# A604F.net
KiCad netlist of a schematic drawn in EAGLE
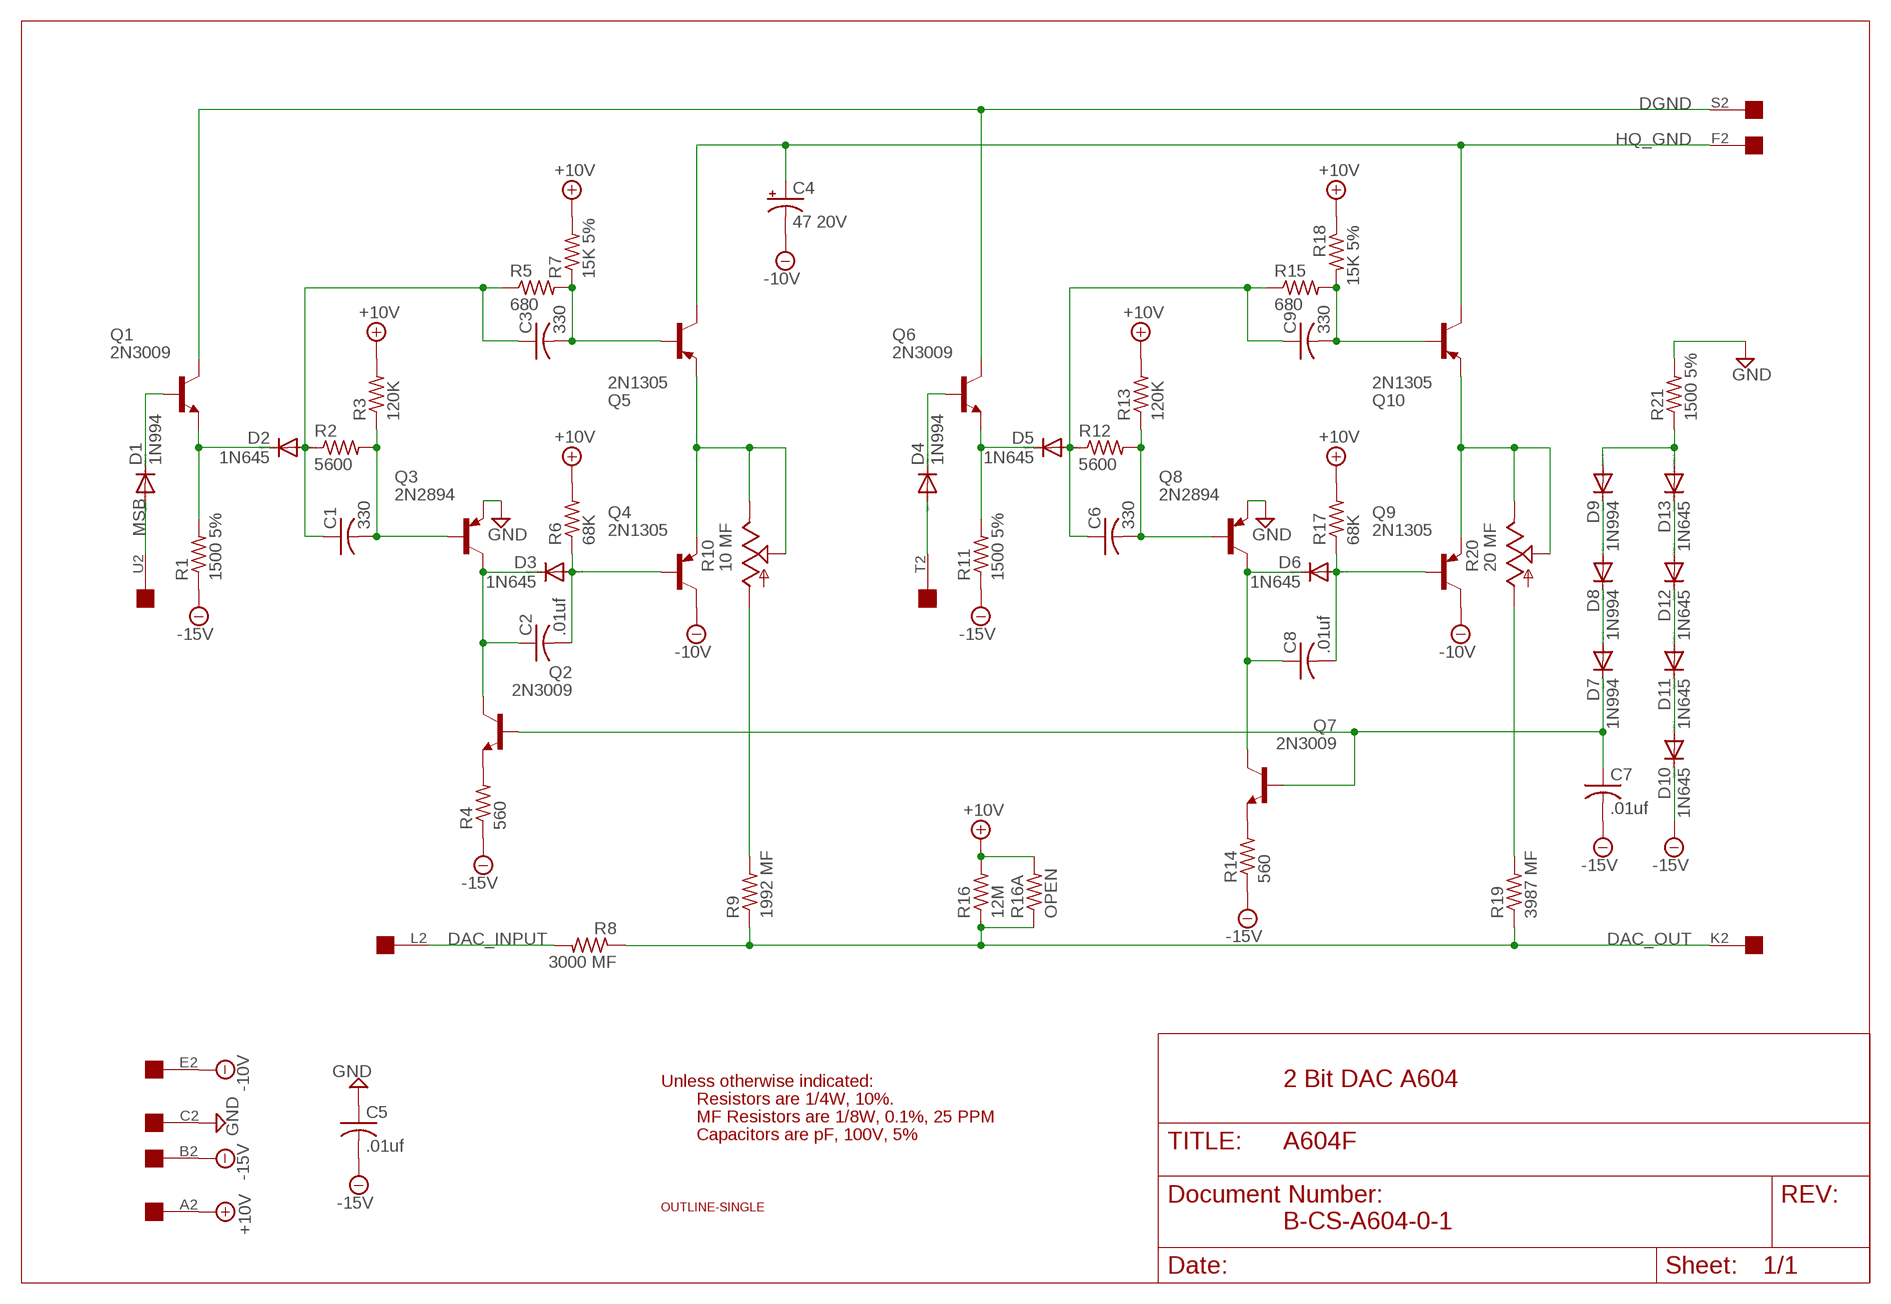
[diagram p0: schematic, sheet 1]

(export (version "E")
  (design (tool "Eeschema 10.0.6"))
  (components
    (comp (ref "C1")
      (value "330")
      (footprint "eagle-import:C075-032X103")
      (libsource (lib "eagle-import") (part "C-US075-032X103"))
    )
    (comp (ref "C2")
      (value ".01uf")
      (footprint "eagle-import:C050-025X075")
      (libsource (lib "eagle-import") (part "C-US050-025X075"))
    )
    (comp (ref "C3")
      (value "330")
      (footprint "eagle-import:C075-032X103")
      (libsource (lib "eagle-import") (part "C-US075-032X103"))
    )
    (comp (ref "C4")
      (value "47 20V")
      (footprint "eagle-import:E12-8")
      (libsource (lib "eagle-import") (part "CPOL-USE20-8AXIAL"))
    )
    (comp (ref "C5")
      (value ".01uf")
      (footprint "eagle-import:C050-025X075")
      (libsource (lib "eagle-import") (part "C-US050-025X075"))
    )
    (comp (ref "C6")
      (value "330")
      (footprint "eagle-import:C075-032X103")
      (libsource (lib "eagle-import") (part "C-US075-032X103"))
    )
    (comp (ref "C7")
      (value ".01uf")
      (footprint "eagle-import:C050-025X075")
      (libsource (lib "eagle-import") (part "C-US050-025X075"))
    )
    (comp (ref "C8")
      (value ".01uf")
      (footprint "eagle-import:C050-025X075")
      (libsource (lib "eagle-import") (part "C-US050-025X075"))
    )
    (comp (ref "C9")
      (value "330")
      (footprint "eagle-import:C075-032X103")
      (libsource (lib "eagle-import") (part "C-US075-032X103"))
    )
    (comp (ref "D1")
      (value "1N994")
      (footprint "eagle-import:DO35-10")
      (libsource (lib "eagle-import") (part "1N4148DO35-10"))
    )
    (comp (ref "D2")
      (value "1N645")
      (footprint "eagle-import:DO35-10")
      (libsource (lib "eagle-import") (part "1N4148DO35-10"))
    )
    (comp (ref "D3")
      (value "1N645")
      (footprint "eagle-import:DO35-10")
      (libsource (lib "eagle-import") (part "1N4148DO35-10"))
    )
    (comp (ref "D4")
      (value "1N994")
      (footprint "eagle-import:DO35-10")
      (libsource (lib "eagle-import") (part "1N4148DO35-10"))
    )
    (comp (ref "D5")
      (value "1N645")
      (footprint "eagle-import:DO35-10")
      (libsource (lib "eagle-import") (part "1N4148DO35-10"))
    )
    (comp (ref "D6")
      (value "1N645")
      (footprint "eagle-import:DO35-10")
      (libsource (lib "eagle-import") (part "1N4148DO35-10"))
    )
    (comp (ref "D7")
      (value "1N994")
      (footprint "eagle-import:DO35-10")
      (libsource (lib "eagle-import") (part "1N4148DO35-10"))
    )
    (comp (ref "D8")
      (value "1N994")
      (footprint "eagle-import:DO35-10")
      (libsource (lib "eagle-import") (part "1N4148DO35-10"))
    )
    (comp (ref "D9")
      (value "1N994")
      (footprint "eagle-import:DO35-10")
      (libsource (lib "eagle-import") (part "1N4148DO35-10"))
    )
    (comp (ref "D10")
      (value "1N645")
      (footprint "eagle-import:DO35-10")
      (libsource (lib "eagle-import") (part "1N4148DO35-10"))
    )
    (comp (ref "D11")
      (value "1N645")
      (footprint "eagle-import:DO35-10")
      (libsource (lib "eagle-import") (part "1N4148DO35-10"))
    )
    (comp (ref "D12")
      (value "1N645")
      (footprint "eagle-import:DO35-10")
      (libsource (lib "eagle-import") (part "1N4148DO35-10"))
    )
    (comp (ref "D13")
      (value "1N645")
      (footprint "eagle-import:DO35-10")
      (libsource (lib "eagle-import") (part "1N4148DO35-10"))
    )
    (comp (ref "Q1")
      (value "2N3009")
      (footprint "eagle-import:TO39")
      (libsource (lib "eagle-import") (part "-NPN-TO39-EBC2N1613"))
    )
    (comp (ref "Q2")
      (value "2N3009")
      (footprint "eagle-import:TO39")
      (libsource (lib "eagle-import") (part "-NPN-TO39-EBC2N1613"))
    )
    (comp (ref "Q3")
      (value "2N2894")
      (footprint "eagle-import:TO39")
      (libsource (lib "eagle-import") (part "2N2904A"))
    )
    (comp (ref "Q4")
      (value "2N1305")
      (footprint "eagle-import:TO39")
      (libsource (lib "eagle-import") (part "2N2904A"))
    )
    (comp (ref "Q5")
      (value "2N1305")
      (footprint "eagle-import:TO39")
      (libsource (lib "eagle-import") (part "2N2904A"))
    )
    (comp (ref "Q6")
      (value "2N3009")
      (footprint "eagle-import:TO39")
      (libsource (lib "eagle-import") (part "-NPN-TO39-EBC2N1613"))
    )
    (comp (ref "Q7")
      (value "2N3009")
      (footprint "eagle-import:TO39")
      (libsource (lib "eagle-import") (part "-NPN-TO39-EBC2N1613"))
    )
    (comp (ref "Q8")
      (value "2N2894")
      (footprint "eagle-import:TO39")
      (libsource (lib "eagle-import") (part "2N2904A"))
    )
    (comp (ref "Q9")
      (value "2N1305")
      (footprint "eagle-import:TO39")
      (libsource (lib "eagle-import") (part "2N2904A"))
    )
    (comp (ref "Q10")
      (value "2N1305")
      (footprint "eagle-import:TO39")
      (libsource (lib "eagle-import") (part "2N2904A"))
    )
    (comp (ref "R1")
      (value "1500 5%")
      (footprint "eagle-import:0207_10")
      (libsource (lib "eagle-import") (part "R-US_0207/10"))
    )
    (comp (ref "R2")
      (value "5600")
      (footprint "eagle-import:0207_10")
      (libsource (lib "eagle-import") (part "R-US_0207/10"))
    )
    (comp (ref "R3")
      (value "120K")
      (footprint "eagle-import:0207_10")
      (libsource (lib "eagle-import") (part "R-US_0207/10"))
    )
    (comp (ref "R4")
      (value "560")
      (footprint "eagle-import:0207_10")
      (libsource (lib "eagle-import") (part "R-US_0207/10"))
    )
    (comp (ref "R5")
      (value "680")
      (footprint "eagle-import:0207_10")
      (libsource (lib "eagle-import") (part "R-US_0207/10"))
    )
    (comp (ref "R6")
      (value "68K")
      (footprint "eagle-import:0207_10")
      (libsource (lib "eagle-import") (part "R-US_0207/10"))
    )
    (comp (ref "R7")
      (value "15K 5%")
      (footprint "eagle-import:0207_10")
      (libsource (lib "eagle-import") (part "R-US_0207/10"))
    )
    (comp (ref "R8")
      (value "3000 MF")
      (footprint "eagle-import:0207_15")
      (libsource (lib "eagle-import") (part "R-US_0207/15"))
    )
    (comp (ref "R9")
      (value "1992 MF")
      (footprint "eagle-import:0207_15")
      (libsource (lib "eagle-import") (part "R-US_0207/15"))
    )
    (comp (ref "R10")
      (value "10 MF")
      (footprint "eagle-import:S75P")
      (libsource (lib "eagle-import") (part "TRIM_US-S75P"))
    )
    (comp (ref "R11")
      (value "1500 5%")
      (footprint "eagle-import:0207_10")
      (libsource (lib "eagle-import") (part "R-US_0207/10"))
    )
    (comp (ref "R12")
      (value "5600")
      (footprint "eagle-import:0207_10")
      (libsource (lib "eagle-import") (part "R-US_0207/10"))
    )
    (comp (ref "R13")
      (value "120K")
      (footprint "eagle-import:0207_10")
      (libsource (lib "eagle-import") (part "R-US_0207/10"))
    )
    (comp (ref "R14")
      (value "560")
      (footprint "eagle-import:0207_10")
      (libsource (lib "eagle-import") (part "R-US_0207/10"))
    )
    (comp (ref "R15")
      (value "680")
      (footprint "eagle-import:0207_10")
      (libsource (lib "eagle-import") (part "R-US_0207/10"))
    )
    (comp (ref "R16")
      (value "12M")
      (footprint "eagle-import:0207_10")
      (libsource (lib "eagle-import") (part "R-US_0207/10"))
    )
    (comp (ref "R16A")
      (value "OPEN")
      (footprint "eagle-import:0207_15")
      (libsource (lib "eagle-import") (part "R-US_0207/15"))
    )
    (comp (ref "R17")
      (value "68K")
      (footprint "eagle-import:0207_10")
      (libsource (lib "eagle-import") (part "R-US_0207/10"))
    )
    (comp (ref "R18")
      (value "15K 5%")
      (footprint "eagle-import:0207_10")
      (libsource (lib "eagle-import") (part "R-US_0207/10"))
    )
    (comp (ref "R19")
      (value "3987 MF")
      (footprint "eagle-import:0207_15")
      (libsource (lib "eagle-import") (part "R-US_0207/15"))
    )
    (comp (ref "R20")
      (value "20 MF")
      (footprint "eagle-import:S75P")
      (libsource (lib "eagle-import") (part "TRIM_US-S75P"))
    )
    (comp (ref "R21")
      (value "1500 5%")
      (footprint "eagle-import:0207_10")
      (libsource (lib "eagle-import") (part "R-US_0207/10"))
    )
    (comp (ref "U$1")
      (value "OUTLINE-SINGLE")
      (footprint "eagle-import:SINGLE")
      (libsource (lib "eagle-import") (part "OUTLINE-SINGLE"))
    )
    (comp (ref "U$3")
      (value "EDGE-1")
      (footprint "eagle-import:EDGE-CON1")
      (libsource (lib "eagle-import") (part "EDGE-1"))
    )
  )
  (nets
    (net (code "1") (name "+10V") (class "Default")
      (node (ref "R13") (pin "2") (pinfunction "2_2") (pintype "passive"))
      (node (ref "R16") (pin "2") (pinfunction "2_2") (pintype "passive"))
      (node (ref "R16A") (pin "2") (pinfunction "2_2") (pintype "passive"))
      (node (ref "R17") (pin "2") (pinfunction "2_2") (pintype "passive"))
      (node (ref "R18") (pin "1") (pinfunction "1_1") (pintype "passive"))
      (node (ref "R3") (pin "2") (pinfunction "2_2") (pintype "passive"))
      (node (ref "R6") (pin "2") (pinfunction "2_2") (pintype "passive"))
      (node (ref "R7") (pin "2") (pinfunction "2_2") (pintype "passive"))
      (node (ref "U$3") (pin "A2") (pinfunction "1_A2") (pintype "bidirectional"))
    )
    (net (code "2") (name "-10V") (class "Default")
      (node (ref "C4") (pin "-") (pinfunction "-_-") (pintype "passive"))
      (node (ref "Q4") (pin "3") (pinfunction "C_3") (pintype "passive"))
      (node (ref "Q9") (pin "3") (pinfunction "C_3") (pintype "passive"))
      (node (ref "U$3") (pin "E2") (pinfunction "1_E2") (pintype "bidirectional"))
    )
    (net (code "3") (name "-15V") (class "Default")
      (node (ref "C5") (pin "2") (pinfunction "2_2") (pintype "passive"))
      (node (ref "C7") (pin "2") (pinfunction "2_2") (pintype "passive"))
      (node (ref "D10") (pin "C") (pinfunction "C_C") (pintype "passive"))
      (node (ref "R1") (pin "1") (pinfunction "1_1") (pintype "passive"))
      (node (ref "R11") (pin "1") (pinfunction "1_1") (pintype "passive"))
      (node (ref "R14") (pin "1") (pinfunction "1_1") (pintype "passive"))
      (node (ref "R4") (pin "1") (pinfunction "1_1") (pintype "passive"))
      (node (ref "U$3") (pin "B2") (pinfunction "1_B2") (pintype "bidirectional"))
    )
    (net (code "4") (name "/DAC_INPUT") (class "Default")
      (node (ref "R8") (pin "2") (pinfunction "2_2") (pintype "passive"))
      (node (ref "U$3") (pin "L2") (pinfunction "1_L2") (pintype "bidirectional"))
    )
    (net (code "5") (name "/DAC_OUT") (class "Default")
      (node (ref "R16") (pin "1") (pinfunction "1_1") (pintype "passive"))
      (node (ref "R16A") (pin "1") (pinfunction "1_1") (pintype "passive"))
      (node (ref "R19") (pin "1") (pinfunction "1_1") (pintype "passive"))
      (node (ref "R8") (pin "1") (pinfunction "1_1") (pintype "passive"))
      (node (ref "R9") (pin "1") (pinfunction "1_1") (pintype "passive"))
      (node (ref "U$3") (pin "K2") (pinfunction "1_K2") (pintype "bidirectional"))
    )
    (net (code "6") (name "/DGND") (class "Default")
      (node (ref "Q1") (pin "3") (pinfunction "C_3") (pintype "passive"))
      (node (ref "Q6") (pin "3") (pinfunction "C_3") (pintype "passive"))
      (node (ref "U$3") (pin "S2") (pinfunction "1_S2") (pintype "bidirectional"))
    )
    (net (code "7") (name "/HQ_GND") (class "Default")
      (node (ref "C4") (pin "+") (pinfunction "+_+") (pintype "passive"))
      (node (ref "Q10") (pin "3") (pinfunction "C_3") (pintype "passive"))
      (node (ref "Q5") (pin "3") (pinfunction "C_3") (pintype "passive"))
      (node (ref "U$3") (pin "F2") (pinfunction "1_F2") (pintype "bidirectional"))
    )
    (net (code "8") (name "/MSB") (class "Default")
      (node (ref "D1") (pin "A") (pinfunction "A_A") (pintype "passive"))
      (node (ref "U$3") (pin "U2") (pinfunction "1_U2") (pintype "bidirectional"))
    )
    (net (code "9") (name "GND") (class "Default")
      (node (ref "C5") (pin "1") (pinfunction "1_1") (pintype "passive"))
      (node (ref "Q3") (pin "1") (pinfunction "E_1") (pintype "passive"))
      (node (ref "Q8") (pin "1") (pinfunction "E_1") (pintype "passive"))
      (node (ref "R21") (pin "2") (pinfunction "2_2") (pintype "passive"))
      (node (ref "U$3") (pin "C2") (pinfunction "1_C2") (pintype "bidirectional"))
    )
    (net (code "10") (name "Net-(C1-Pad1)") (class "Default")
      (node (ref "C1") (pin "1") (pinfunction "1_1") (pintype "passive"))
      (node (ref "C3") (pin "1") (pinfunction "1_1") (pintype "passive"))
      (node (ref "D2") (pin "A") (pinfunction "A_A") (pintype "passive"))
      (node (ref "R2") (pin "1") (pinfunction "1_1") (pintype "passive"))
      (node (ref "R5") (pin "1") (pinfunction "1_1") (pintype "passive"))
    )
    (net (code "11") (name "Net-(C6-Pad1)") (class "Default")
      (node (ref "C6") (pin "1") (pinfunction "1_1") (pintype "passive"))
      (node (ref "C9") (pin "1") (pinfunction "1_1") (pintype "passive"))
      (node (ref "D5") (pin "A") (pinfunction "A_A") (pintype "passive"))
      (node (ref "R12") (pin "1") (pinfunction "1_1") (pintype "passive"))
      (node (ref "R15") (pin "1") (pinfunction "1_1") (pintype "passive"))
    )
    (net (code "12") (name "Net-(D7-PadA)") (class "Default")
      (node (ref "D7") (pin "A") (pinfunction "A_A") (pintype "passive"))
      (node (ref "D8") (pin "C") (pinfunction "C_C") (pintype "passive"))
    )
    (net (code "13") (name "Net-(D8-PadA)") (class "Default")
      (node (ref "D8") (pin "A") (pinfunction "A_A") (pintype "passive"))
      (node (ref "D9") (pin "C") (pinfunction "C_C") (pintype "passive"))
    )
    (net (code "14") (name "Net-(D10-PadA)") (class "Default")
      (node (ref "D10") (pin "A") (pinfunction "A_A") (pintype "passive"))
      (node (ref "D11") (pin "C") (pinfunction "C_C") (pintype "passive"))
    )
    (net (code "15") (name "Net-(D11-PadA)") (class "Default")
      (node (ref "D11") (pin "A") (pinfunction "A_A") (pintype "passive"))
      (node (ref "D12") (pin "C") (pinfunction "C_C") (pintype "passive"))
    )
    (net (code "16") (name "Net-(D12-PadA)") (class "Default")
      (node (ref "D12") (pin "A") (pinfunction "A_A") (pintype "passive"))
      (node (ref "D13") (pin "C") (pinfunction "C_C") (pintype "passive"))
    )
    (net (code "17") (name "Net-(D13-PadA)") (class "Default")
      (node (ref "D13") (pin "A") (pinfunction "A_A") (pintype "passive"))
      (node (ref "D9") (pin "A") (pinfunction "A_A") (pintype "passive"))
      (node (ref "R21") (pin "1") (pinfunction "1_1") (pintype "passive"))
    )
    (net (code "18") (name "Net-(Q1-B)") (class "Default")
      (node (ref "D1") (pin "C") (pinfunction "C_C") (pintype "passive"))
      (node (ref "Q1") (pin "2") (pinfunction "B_2") (pintype "passive"))
    )
    (net (code "19") (name "Net-(Q1-E)") (class "Default")
      (node (ref "D2") (pin "C") (pinfunction "C_C") (pintype "passive"))
      (node (ref "Q1") (pin "1") (pinfunction "E_1") (pintype "passive"))
      (node (ref "R1") (pin "2") (pinfunction "2_2") (pintype "passive"))
    )
    (net (code "20") (name "Net-(Q2-B)") (class "Default")
      (node (ref "C7") (pin "1") (pinfunction "1_1") (pintype "passive"))
      (node (ref "D7") (pin "C") (pinfunction "C_C") (pintype "passive"))
      (node (ref "Q2") (pin "2") (pinfunction "B_2") (pintype "passive"))
      (node (ref "Q7") (pin "2") (pinfunction "B_2") (pintype "passive"))
    )
    (net (code "21") (name "Net-(Q2-C)") (class "Default")
      (node (ref "C2") (pin "1") (pinfunction "1_1") (pintype "passive"))
      (node (ref "D3") (pin "C") (pinfunction "C_C") (pintype "passive"))
      (node (ref "Q2") (pin "3") (pinfunction "C_3") (pintype "passive"))
      (node (ref "Q3") (pin "3") (pinfunction "C_3") (pintype "passive"))
    )
    (net (code "22") (name "Net-(Q2-E)") (class "Default")
      (node (ref "Q2") (pin "1") (pinfunction "E_1") (pintype "passive"))
      (node (ref "R4") (pin "2") (pinfunction "2_2") (pintype "passive"))
    )
    (net (code "23") (name "Net-(Q3-B)") (class "Default")
      (node (ref "C1") (pin "2") (pinfunction "2_2") (pintype "passive"))
      (node (ref "Q3") (pin "2") (pinfunction "B_2") (pintype "passive"))
      (node (ref "R2") (pin "2") (pinfunction "2_2") (pintype "passive"))
      (node (ref "R3") (pin "1") (pinfunction "1_1") (pintype "passive"))
    )
    (net (code "24") (name "Net-(Q4-B)") (class "Default")
      (node (ref "C2") (pin "2") (pinfunction "2_2") (pintype "passive"))
      (node (ref "D3") (pin "A") (pinfunction "A_A") (pintype "passive"))
      (node (ref "Q4") (pin "2") (pinfunction "B_2") (pintype "passive"))
      (node (ref "R6") (pin "1") (pinfunction "1_1") (pintype "passive"))
    )
    (net (code "25") (name "Net-(Q4-E)") (class "Default")
      (node (ref "Q4") (pin "1") (pinfunction "E_1") (pintype "passive"))
      (node (ref "Q5") (pin "1") (pinfunction "E_1") (pintype "passive"))
      (node (ref "R10") (pin "E") (pinfunction "E_E") (pintype "passive"))
      (node (ref "R10") (pin "S") (pinfunction "S_S") (pintype "passive"))
    )
    (net (code "26") (name "Net-(Q5-B)") (class "Default")
      (node (ref "C3") (pin "2") (pinfunction "2_2") (pintype "passive"))
      (node (ref "Q5") (pin "2") (pinfunction "B_2") (pintype "passive"))
      (node (ref "R5") (pin "2") (pinfunction "2_2") (pintype "passive"))
      (node (ref "R7") (pin "1") (pinfunction "1_1") (pintype "passive"))
    )
    (net (code "27") (name "Net-(Q6-B)") (class "Default")
      (node (ref "D4") (pin "C") (pinfunction "C_C") (pintype "passive"))
      (node (ref "Q6") (pin "2") (pinfunction "B_2") (pintype "passive"))
    )
    (net (code "28") (name "Net-(Q6-E)") (class "Default")
      (node (ref "D5") (pin "C") (pinfunction "C_C") (pintype "passive"))
      (node (ref "Q6") (pin "1") (pinfunction "E_1") (pintype "passive"))
      (node (ref "R11") (pin "2") (pinfunction "2_2") (pintype "passive"))
    )
    (net (code "29") (name "Net-(Q7-C)") (class "Default")
      (node (ref "C8") (pin "1") (pinfunction "1_1") (pintype "passive"))
      (node (ref "D6") (pin "C") (pinfunction "C_C") (pintype "passive"))
      (node (ref "Q7") (pin "3") (pinfunction "C_3") (pintype "passive"))
      (node (ref "Q8") (pin "3") (pinfunction "C_3") (pintype "passive"))
    )
    (net (code "30") (name "Net-(Q7-E)") (class "Default")
      (node (ref "Q7") (pin "1") (pinfunction "E_1") (pintype "passive"))
      (node (ref "R14") (pin "2") (pinfunction "2_2") (pintype "passive"))
    )
    (net (code "31") (name "Net-(Q8-B)") (class "Default")
      (node (ref "C6") (pin "2") (pinfunction "2_2") (pintype "passive"))
      (node (ref "Q8") (pin "2") (pinfunction "B_2") (pintype "passive"))
      (node (ref "R12") (pin "2") (pinfunction "2_2") (pintype "passive"))
      (node (ref "R13") (pin "1") (pinfunction "1_1") (pintype "passive"))
    )
    (net (code "32") (name "Net-(Q9-B)") (class "Default")
      (node (ref "C8") (pin "2") (pinfunction "2_2") (pintype "passive"))
      (node (ref "D6") (pin "A") (pinfunction "A_A") (pintype "passive"))
      (node (ref "Q9") (pin "2") (pinfunction "B_2") (pintype "passive"))
      (node (ref "R17") (pin "1") (pinfunction "1_1") (pintype "passive"))
    )
    (net (code "33") (name "Net-(Q10-B)") (class "Default")
      (node (ref "C9") (pin "2") (pinfunction "2_2") (pintype "passive"))
      (node (ref "Q10") (pin "2") (pinfunction "B_2") (pintype "passive"))
      (node (ref "R15") (pin "2") (pinfunction "2_2") (pintype "passive"))
      (node (ref "R18") (pin "2") (pinfunction "2_2") (pintype "passive"))
    )
    (net (code "34") (name "Net-(Q10-E)") (class "Default")
      (node (ref "Q10") (pin "1") (pinfunction "E_1") (pintype "passive"))
      (node (ref "Q9") (pin "1") (pinfunction "E_1") (pintype "passive"))
      (node (ref "R20") (pin "E") (pinfunction "E_E") (pintype "passive"))
      (node (ref "R20") (pin "S") (pinfunction "S_S") (pintype "passive"))
    )
    (net (code "35") (name "Net-(R10-PadA)") (class "Default")
      (node (ref "R10") (pin "A") (pinfunction "A_A") (pintype "passive"))
      (node (ref "R9") (pin "2") (pinfunction "2_2") (pintype "passive"))
    )
    (net (code "36") (name "Net-(R19-Pad2)") (class "Default")
      (node (ref "R19") (pin "2") (pinfunction "2_2") (pintype "passive"))
      (node (ref "R20") (pin "A") (pinfunction "A_A") (pintype "passive"))
    )
    (net (code "37") (name "Net-(U$3P-1)") (class "Default")
      (node (ref "D4") (pin "A") (pinfunction "A_A") (pintype "passive"))
      (node (ref "U$3") (pin "T2") (pinfunction "1_T2") (pintype "bidirectional"))
    )
  )
)
